# Remie_Schematic.net
KiCad netlist of a schematic drawn in Altium Designer
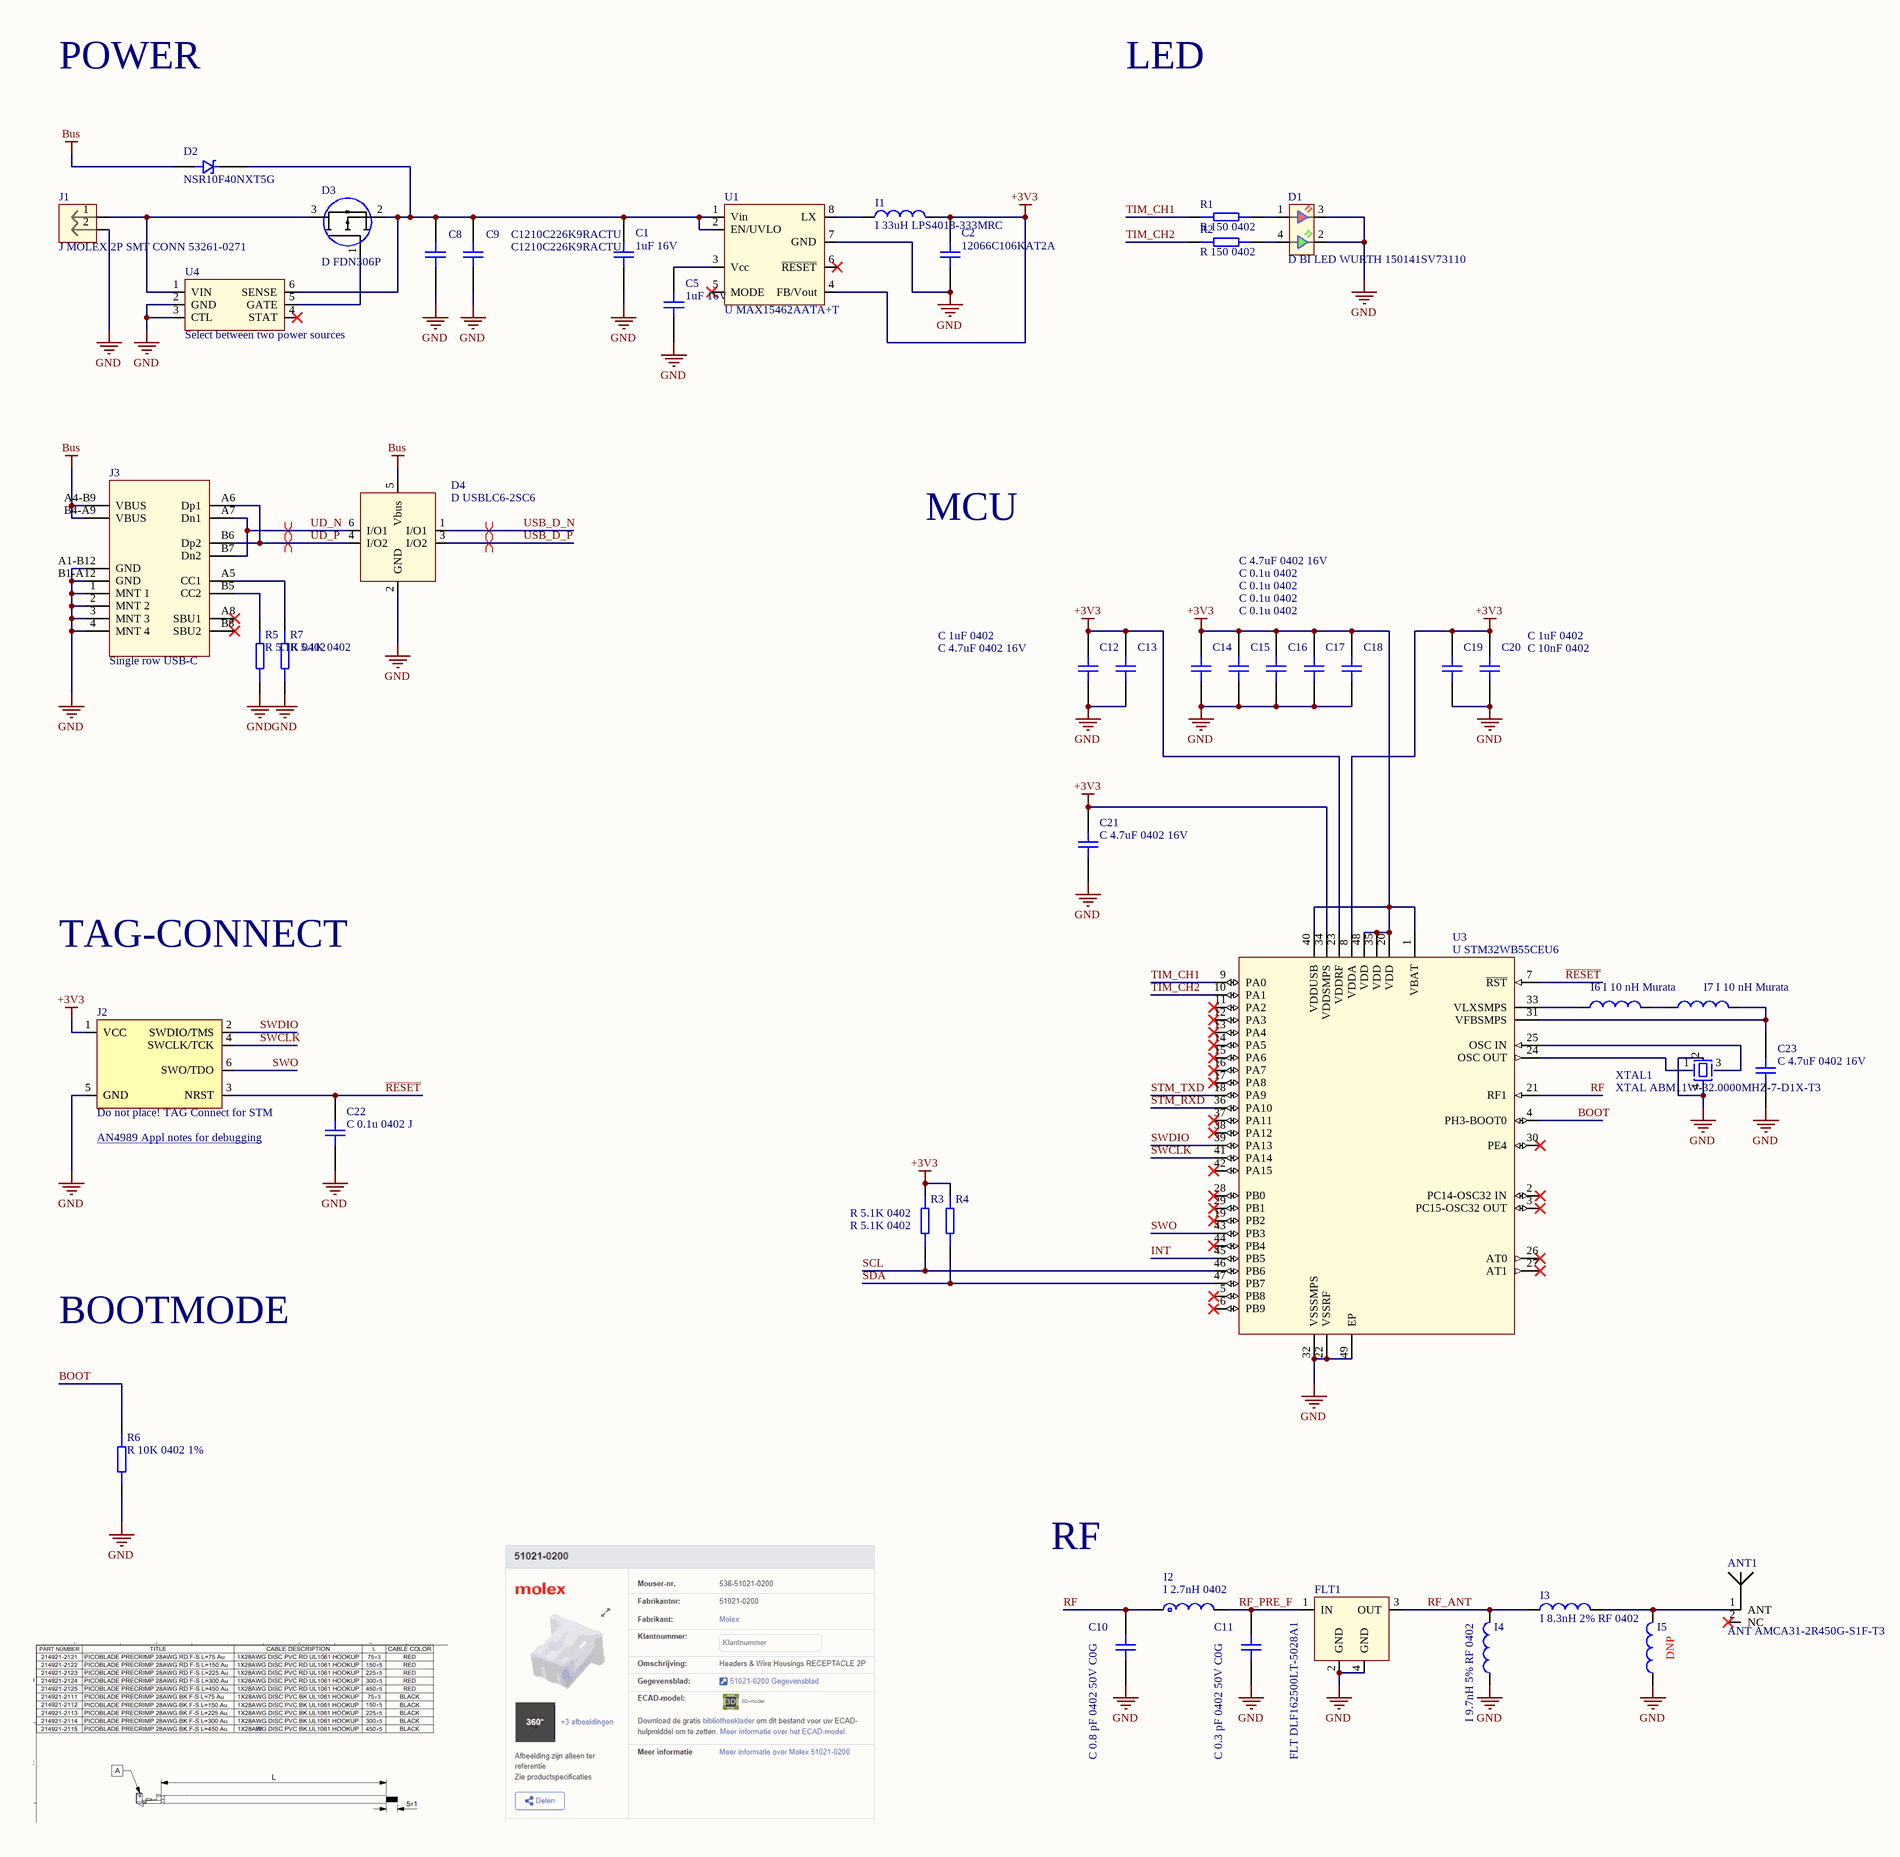
[diagram p0: Remie_Schematic.SchDoc, left]
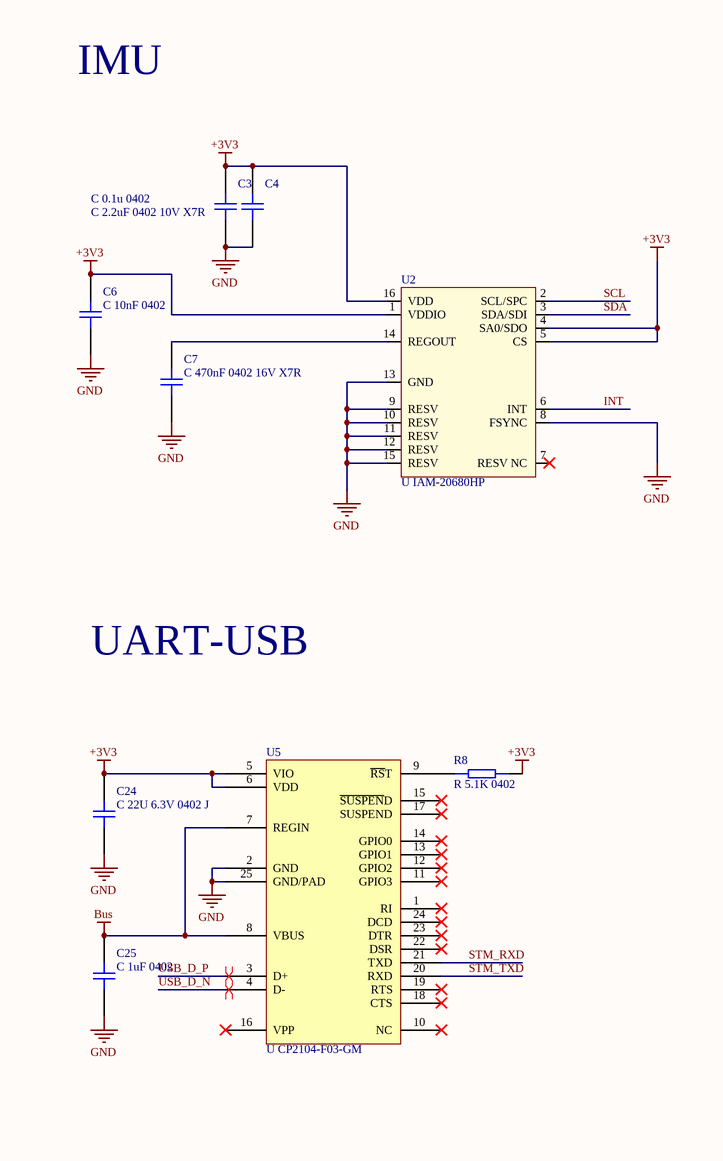
[diagram p1: Remie_Schematic.SchDoc, right]

(export (version "E")
  (design (tool "Eeschema 10.0.6"))
  (components
    (comp (ref "ANT1")
      (value "ANT AMCA31-2R450G-S1F-T3")
      (footprint "ABRACON AMCA31")
      (description "Chip Dielectric Antenna; 1dBi; 2450MHz; T/R ¦ Abracon AMCA31-2R450G-S1F-T3")
      (fields
        (field (name "MANUFACTURER") "Abracon")
        (field (name "MANUFACTURER PART NUMBER") "AMCA31-2R450G-S1F-T3")
      )
      (libsource (lib "Schlib2") (part "ANT AMCA31-2R450G-S1F-T3"))
    )
    (comp (ref "C1")
      (value "1uF 16V")
      (footprint "C0805")
      (description "Multilayer Ceramic Capacitor, 1 uF, 16 V, ± 10%, X7R, 0805 [2012 Metric]")
      (fields
        (field (name "MANUFACTURER") "KEMET")
        (field (name "MANUFACTURER PART NUMBER") "C0805C105K4RACTU")
      )
      (libsource (lib "Schlib2") (part "C 1U 0805 X7R 16V"))
    )
    (comp (ref "C2")
      (value "12066C106KAT2A")
      (footprint "C1206")
      (description "1206 6.3 V 10 uF ±10% Tolerance X7R SMT Multilayer Ceramic Capacitor")
      (fields (field (name "MANUFACTURER") "Kyocera AVX") (field (name "TOLERANCE") "10%"))
      (libsource (lib "Schlib2") (part "C 10uF 1206 6.3V X7R"))
    )
    (comp (ref "C3")
      (value "C 0.1u 0402")
      (footprint "C0402")
      (description "Multilayer Ceramic Capacitor, 0.1 uF, 50 V, ± 10%, X7R, 0402 [1005 Metric]")
      (fields
        (field (name "MANUFACTURER") "Samsung")
        (field (name "MANUFACTURER PART NUMBER") "CL05B104KB54PNC")
      )
      (libsource (lib "Schlib2") (part "C 0.1u 0402"))
    )
    (comp (ref "C4")
      (value "C 2.2uF 0402 10V X7R")
      (footprint "C0402")
      (description "Multilayer Ceramic Capacitor, 2.2 uF, 10 V, ± 10%, X7R, 0402 [1005 Metric] CC0402KRX5R7BB225")
      (fields
        (field (name "MANUFACTURER") "Yageo")
        (field (name "MANUFACTURER PART NUMBER") "CC0402KRX5R7BB225")
      )
      (libsource (lib "Schlib2") (part "C 2.2uF 0402 10V X7R"))
    )
    (comp (ref "C5")
      (value "1uF 16V")
      (footprint "C0805")
      (description "Multilayer Ceramic Capacitor, 1 uF, 16 V, ± 10%, X7R, 0805 [2012 Metric]")
      (fields
        (field (name "MANUFACTURER") "KEMET")
        (field (name "MANUFACTURER PART NUMBER") "C0805C105K4RACTU")
      )
      (libsource (lib "Schlib2") (part "C 1U 0805 X7R 16V"))
    )
    (comp (ref "C6")
      (value "C 10nF 0402")
      (footprint "C0402")
      (description "Multilayer Ceramic Capacitor, 0.01 uF, 50 V, ± 10%, X7R, 0402 [1005 Metric]")
      (fields
        (field (name "MANUFACTURER") "Samsung")
        (field (name "MANUFACTURER PART NUMBER") "CL05B103KB5NNNC")
      )
      (libsource (lib "Schlib2") (part "C 10nF 0402"))
    )
    (comp (ref "C7")
      (value "C 470nF 0402 16V X7R")
      (footprint "C0402")
      (description "Multilayer Ceramic Capacitor, 0.47 uF, 16 V, ± 10%, X7R, 0402 [1005 Metric] CC0402KRX7R5BB474")
      (fields
        (field (name "MANUFACTURER") "Yageo")
        (field (name "MANUFACTURER PART NUMBER") "CC0402KRX7R5BB474")
      )
      (libsource (lib "Schlib2") (part "C 470nF 0402 16V X7R"))
    )
    (comp (ref "C8")
      (value "C1210C226K9RACTU")
      (footprint "C1210")
      (description "Cap Ceramic 22uF 6.3V X7R 10% SMD 1210 125C Plastic T/R")
      (fields (field (name "MANUFACTURER") "KEMET") (field (name "TOLERANCE") "10%"))
      (libsource (lib "Schlib2") (part "C 22uF 1210 X7R 6.3V"))
    )
    (comp (ref "C9")
      (value "C1210C226K9RACTU")
      (footprint "C1210")
      (description "Cap Ceramic 22uF 6.3V X7R 10% SMD 1210 125C Plastic T/R")
      (fields (field (name "MANUFACTURER") "KEMET") (field (name "TOLERANCE") "10%"))
      (libsource (lib "Schlib2") (part "C 22uF 1210 X7R 6.3V"))
    )
    (comp (ref "C10")
      (value "C 0.8 pF 0402 50V C0G")
      (footprint "C0402")
      (fields
        (field (name "MANUFACTURER") "Murata")
        (field (name "MANUFACTURER PART NUMBER") "GRM1555C1HR80BA01D")
        (field (name "VOLTAGE") "50V")
      )
      (libsource (lib "Schlib2") (part "C 0.8 pF 0402 50V C0G"))
    )
    (comp (ref "C11")
      (value "C 0.3 pF 0402 50V C0G")
      (footprint "C0402")
      (description "Cap Ceramic 0.3pF 50V C0G 0.05pF Pad SMD 0402 125°C T/R")
      (fields
        (field (name "MANUFACTURER") "Murata")
        (field (name "MANUFACTURER PART NUMBER") "GRM1555C1HR30WA01D")
      )
      (libsource (lib "Schlib2") (part "C 0.3 pF 0402 50V C0G"))
    )
    (comp (ref "C12")
      (value "C 1uF 0402")
      (footprint "C0402")
      (description "Multilayer Ceramic Capacitor, 1 uF, 10 V, ± 10%, X5R, 0402 [1005 Metric]")
      (fields
        (field (name "MANUFACTURER") "Samsung")
        (field (name "MANUFACTURER PART NUMBER") "CL05A105KP5NNNC")
      )
      (libsource (lib "Schlib2") (part "C 1uF 0402"))
    )
    (comp (ref "C13")
      (value "C 4.7uF 0402 16V")
      (footprint "C0402")
      (description "Multilayer Ceramic Capacitor, 4.7 uF, 16 V, ± 20%, X5R, 0402 [1005 Metric] CL05A475MO5NUNC")
      (fields
        (field (name "MANUFACTURER") "Samsung")
        (field (name "MANUFACTURER PART NUMBER") "CL05A475MO5NUNC")
      )
      (libsource (lib "Schlib2") (part "C 4.7uF 0402 16V"))
    )
    (comp (ref "C14")
      (value "C 4.7uF 0402 16V")
      (footprint "C0402")
      (description "Multilayer Ceramic Capacitor, 4.7 uF, 16 V, ± 20%, X5R, 0402 [1005 Metric] CL05A475MO5NUNC")
      (fields
        (field (name "MANUFACTURER") "Samsung")
        (field (name "MANUFACTURER PART NUMBER") "CL05A475MO5NUNC")
      )
      (libsource (lib "Schlib2") (part "C 4.7uF 0402 16V"))
    )
    (comp (ref "C15")
      (value "C 0.1u 0402")
      (footprint "C0402")
      (description "Multilayer Ceramic Capacitor, 0.1 uF, 50 V, ± 10%, X7R, 0402 [1005 Metric]")
      (fields
        (field (name "MANUFACTURER") "Samsung")
        (field (name "MANUFACTURER PART NUMBER") "CL05B104KB54PNC")
      )
      (libsource (lib "Schlib2") (part "C 0.1u 0402"))
    )
    (comp (ref "C16")
      (value "C 0.1u 0402")
      (footprint "C0402")
      (description "Multilayer Ceramic Capacitor, 0.1 uF, 50 V, ± 10%, X7R, 0402 [1005 Metric]")
      (fields
        (field (name "MANUFACTURER") "Samsung")
        (field (name "MANUFACTURER PART NUMBER") "CL05B104KB54PNC")
      )
      (libsource (lib "Schlib2") (part "C 0.1u 0402"))
    )
    (comp (ref "C17")
      (value "C 0.1u 0402")
      (footprint "C0402")
      (description "Multilayer Ceramic Capacitor, 0.1 uF, 50 V, ± 10%, X7R, 0402 [1005 Metric]")
      (fields
        (field (name "MANUFACTURER") "Samsung")
        (field (name "MANUFACTURER PART NUMBER") "CL05B104KB54PNC")
      )
      (libsource (lib "Schlib2") (part "C 0.1u 0402"))
    )
    (comp (ref "C18")
      (value "C 0.1u 0402")
      (footprint "C0402")
      (description "Multilayer Ceramic Capacitor, 0.1 uF, 50 V, ± 10%, X7R, 0402 [1005 Metric]")
      (fields
        (field (name "MANUFACTURER") "Samsung")
        (field (name "MANUFACTURER PART NUMBER") "CL05B104KB54PNC")
      )
      (libsource (lib "Schlib2") (part "C 0.1u 0402"))
    )
    (comp (ref "C19")
      (value "C 1uF 0402")
      (footprint "C0402")
      (description "Multilayer Ceramic Capacitor, 1 uF, 10 V, ± 10%, X5R, 0402 [1005 Metric]")
      (fields
        (field (name "MANUFACTURER") "Samsung")
        (field (name "MANUFACTURER PART NUMBER") "CL05A105KP5NNNC")
      )
      (libsource (lib "Schlib2") (part "C 1uF 0402"))
    )
    (comp (ref "C20")
      (value "C 10nF 0402")
      (footprint "C0402")
      (description "Multilayer Ceramic Capacitor, 0.01 uF, 50 V, ± 10%, X7R, 0402 [1005 Metric]")
      (fields
        (field (name "MANUFACTURER") "Samsung")
        (field (name "MANUFACTURER PART NUMBER") "CL05B103KB5NNNC")
      )
      (libsource (lib "Schlib2") (part "C 10nF 0402"))
    )
    (comp (ref "C21")
      (value "C 4.7uF 0402 16V")
      (footprint "C0402")
      (description "Multilayer Ceramic Capacitor, 4.7 uF, 16 V, ± 20%, X5R, 0402 [1005 Metric] CL05A475MO5NUNC")
      (fields
        (field (name "MANUFACTURER") "Samsung")
        (field (name "MANUFACTURER PART NUMBER") "CL05A475MO5NUNC")
      )
      (libsource (lib "Schlib2") (part "C 4.7uF 0402 16V"))
    )
    (comp (ref "C22")
      (value "C 0.1u 0402 J")
      (footprint "C0402")
      (description "Cap Ceramic 0.1uF 50V X7R 10% Pad SMD 0402 125C Low ESR Automotive CL05B104KB54PNC")
      (fields
        (field (name "MANUFACTURER") "Samsung")
        (field (name "MANUFACTURER PART NUMBER") "CL05B104KB54PNC")
      )
      (libsource (lib "Schlib2") (part "C 0.1u 0402 J"))
    )
    (comp (ref "C23")
      (value "C 4.7uF 0402 16V")
      (footprint "C0402")
      (description "Multilayer Ceramic Capacitor, 4.7 uF, 16 V, ± 20%, X5R, 0402 [1005 Metric] CL05A475MO5NUNC")
      (fields
        (field (name "MANUFACTURER") "Samsung")
        (field (name "MANUFACTURER PART NUMBER") "CL05A475MO5NUNC")
      )
      (libsource (lib "Schlib2") (part "C 4.7uF 0402 16V"))
    )
    (comp (ref "C24")
      (value "C 22U 6.3V 0402 J")
      (footprint "C0402")
      (description "CAP CER 22F 6.3V X5R 0402 CM05X5R226M06AH080")
      (fields
        (field (name "MANUFACTURER") "Kyocera AVX")
        (field (name "MANUFACTURER PART NUMBER") "CM05X5R226M06AH080")
      )
      (libsource (lib "Schlib2") (part "C 22U 6.3V 0402 J"))
    )
    (comp (ref "C25")
      (value "C 1uF 0402")
      (footprint "C0402")
      (description "Multilayer Ceramic Capacitor, 1 uF, 10 V, ± 10%, X5R, 0402 [1005 Metric]")
      (fields
        (field (name "MANUFACTURER") "Samsung")
        (field (name "MANUFACTURER PART NUMBER") "CL05A105KP5NNNC")
      )
      (libsource (lib "Schlib2") (part "C 1uF 0402"))
    )
    (comp (ref "D1")
      (value "D BI LED WURTH 150141SV73110")
      (footprint "Wurth 150141SV73110")
      (description "WL-SBTW SMT bi-color TOP LED waterclear")
      (fields
        (field (name "MANUFACTURER") "Wurth Electronics")
        (field (name "MANUFACTURER PART NUMBER") "150141SV73110")
      )
      (libsource (lib "Schlib2") (part "D BI LED WURTH 150141SV73110"))
    )
    (comp (ref "D2")
      (value "NSR10F40NXT5G")
      (footprint "SCHOTTKY NSR10")
      (fields (field (name "MANUFACTURER") "ON Semiconductor"))
      (libsource (lib "Schlib2") (part "D Schottky 1A"))
    )
    (comp (ref "D3")
      (value "D FDN306P")
      (footprint "SOT23")
      (description "P-Channel PowerTrench® MOSFET, 1.8V Specified, -12V, -2.6A, 40mΩ")
      (fields
        (field (name "MANUFACTURER") "ON Semiconductor / Fairchild")
        (field (name "MANUFACTURER PART NUMBER") "FDN306P")
      )
      (libsource (lib "Schlib2") (part "D FDN306P"))
    )
    (comp (ref "D4")
      (value "D USBLC6-2SC6")
      (footprint "SOT23-6L")
      (description "USBLC6 Series 2 Line 6 V Uni / Bi-Directional ESD Protection - SOT-23-6")
      (fields
        (field (name "MANUFACTURER") "STMicroelectronics")
        (field (name "MANUFACTURER PART NUMBER") "USBLC6-2SC6")
      )
      (libsource (lib "Schlib2") (part "D USBLC6-2SC6"))
    )
    (comp (ref "FLT1")
      (value "FLT DLF162500LT-5028A1")
      (footprint "TDK DLF Series")
      (description "FILTER, LOW PASS, 2.4GHz to 2.5GHz; Filter Type: Low Pass; Pass Band Frequency: 2.")
      (fields
        (field (name "MANUFACTURER") "TDK")
        (field (name "MANUFACTURER PART NUMBER") "DLF162500LT-5028A1")
      )
      (libsource (lib "Schlib2") (part "FLT DLF162500LT-5028A1"))
    )
    (comp (ref "I1")
      (value "I 33uH LPS4018-333MRC")
      (footprint "COILCRAFT LPS4018")
      (description "Power inductor, shielded, 20/30% tol, SMT, RoHS, lead-free, halogen-free LPS4018-333MRC Isat 0.58A")
      (fields
        (field (name "MANUFACTURER") "Coilcraft")
        (field (name "MANUFACTURER PART NUMBER") "LPS4018-333MRC")
      )
      (libsource (lib "Schlib2") (part "I 33uH LPS4018-333MRC"))
    )
    (comp (ref "I2")
      (value "I 2.7nH 0402")
      (footprint "I0402 POL")
      (description "0402 2.7nH ±0.3nH DCR=120mΩ Q=8@100MHz 800mA SRF=6GHz LQG15HS2N7S02D")
      (fields
        (field (name "MANUFACTURER") "Murata")
        (field (name "MANUFACTURER PART NUMBER") "LQG15HS2N7S02D")
      )
      (libsource (lib "Schlib2") (part "I 2.7nH 0402"))
    )
    (comp (ref "I3")
      (value "I 8.3nH 2% RF 0402")
      (footprint "R0402")
      (description "Ind Chip Wirewound 8.3nH 0.2nH 0402 Paper T/R LQW15AN8N3C1ZD")
      (fields
        (field (name "MANUFACTURER") "Murata")
        (field (name "MANUFACTURER PART NUMBER") "LQW15AN8N3C1ZD")
      )
      (libsource (lib "Schlib2") (part "I 8.3nH 2% RF 0402"))
    )
    (comp (ref "I4")
      (value "I 9.7nH 5% RF 0402")
      (footprint "R0402")
      (description "Ind Chip Wirewound 9.7nH 5% 0402 Paper T/R LQW15AN9N7J0ZD")
      (fields
        (field (name "MANUFACTURER") "Murata")
        (field (name "MANUFACTURER PART NUMBER") "LQW15AN9N7J0ZD")
      )
      (libsource (lib "Schlib2") (part "I 9.7nH 5% RF 0402"))
    )
    (comp (ref "I5")
      (value "I 9.7nH 5% RF 0402")
      (footprint "R0402")
      (description "Ind Chip Wirewound 9.7nH 5% 0402 Paper T/R LQW15AN9N7J0ZD")
      (fields
        (field (name "MANUFACTURER") "Murata")
        (field (name "MANUFACTURER PART NUMBER") "LQW15AN9N7J0ZD")
      )
      (libsource (lib "Schlib2") (part "I 9.7nH 5% RF 0402"))
    )
    (comp (ref "I6")
      (value "I 10 nH Murata")
      (footprint "MURATA LQG15XXX IND")
      (fields
        (field (name "MANUFACTURER") "Murata")
        (field (name "MANUFACTURER PART NUMBER") "LQG15WZ10NJ02D")
        (field (name "TOLERANCE") "5%")
      )
      (libsource (lib "Schlib2") (part "I 10 nH Murata"))
    )
    (comp (ref "I7")
      (value "I 10 nH Murata")
      (footprint "MURATA LQG15XXX IND")
      (fields
        (field (name "MANUFACTURER") "Murata")
        (field (name "MANUFACTURER PART NUMBER") "LQG15WZ10NJ02D")
        (field (name "TOLERANCE") "5%")
      )
      (libsource (lib "Schlib2") (part "I 10 nH Murata"))
    )
    (comp (ref "J1")
      (value "J MOLEX 2P SMT CONN 53261-0271")
      (footprint "MOLEX 532610271")
      (description "1.25mm Pitch PicoBlade™ Header, Surface Mount, Right Angle, Lead-Free, 2 Circuits")
      (fields (field (name "MANUFACTURER") "Molex") (field (name "MANUFACTURER PART NUMBER") "53261-0271"))
      (libsource (lib "Schlib2") (part "J MOLEX 2P SMT CONN 53261-0271"))
    )
    (comp (ref "J2")
      (value "Do not place! TAG Connect for STM")
      (footprint "TAG-CONNECT-6")
      (libsource (lib "Schlib2") (part "J TAG for STM TC-2030"))
    )
    (comp (ref "J3")
      (value "Single row USB-C")
      (footprint "FP-USB4105-GF-A-MFG")
      (description "Conn USB 2.0 Type C RCP 24 POS 0.3mm/0.5mm Solder RA SMD 24 Terminal 1 Port T/R")
      (fields
        (field (name "MANUFACTURER") "Global Connector Technology")
        (field (name "MANUFACTURER PART NUMBER") "USB4105-GF-A")
      )
      (libsource (lib "Schlib2") (part "J USB4105-GF-A"))
    )
    (comp (ref "R1")
      (value "R 150 0402")
      (footprint "R0402")
      (description "SMD Chip Resistor, 150 Ohm, ± 1%, 62.5 mW, 0402 [1005 Metric], Thick Film, General Purpose")
      (fields
        (field (name "MANUFACTURER") "Yageo")
        (field (name "MANUFACTURER PART NUMBER") "RC0402FR-07150RL")
      )
      (libsource (lib "Schlib2") (part "R 150 0402"))
    )
    (comp (ref "R2")
      (value "R 150 0402")
      (footprint "R0402")
      (description "SMD Chip Resistor, 150 Ohm, ± 1%, 62.5 mW, 0402 [1005 Metric], Thick Film, General Purpose")
      (fields
        (field (name "MANUFACTURER") "Yageo")
        (field (name "MANUFACTURER PART NUMBER") "RC0402FR-07150RL")
      )
      (libsource (lib "Schlib2") (part "R 150 0402"))
    )
    (comp (ref "R3")
      (value "R 5.1K 0402")
      (footprint "R0402")
      (fields
        (field (name "MANUFACTURER") "Vishay")
        (field (name "MANUFACTURER PART NUMBER") "CRCW04025K10FKED")
        (field (name "TOLERANCE") "1%")
      )
      (libsource (lib "Schlib2") (part "R 5.1K 0402"))
    )
    (comp (ref "R4")
      (value "R 5.1K 0402")
      (footprint "R0402")
      (fields
        (field (name "MANUFACTURER") "Vishay")
        (field (name "MANUFACTURER PART NUMBER") "CRCW04025K10FKED")
        (field (name "TOLERANCE") "1%")
      )
      (libsource (lib "Schlib2") (part "R 5.1K 0402"))
    )
    (comp (ref "R5")
      (value "R 5.1K 0402")
      (footprint "R0402")
      (fields
        (field (name "MANUFACTURER") "Vishay")
        (field (name "MANUFACTURER PART NUMBER") "CRCW04025K10FKED")
        (field (name "TOLERANCE") "1%")
      )
      (libsource (lib "Schlib2") (part "R 5.1K 0402"))
    )
    (comp (ref "R6")
      (value "R 10K 0402 1%")
      (footprint "R0402")
      (description "Res Thick Film 0402 10K Ohm 1% 0.2W(1/5W) ±100ppm/°C Pad SMD Automotive T/R CRCW040210K0FKEDHP")
      (fields
        (field (name "MANUFACTURER") "Vishay Dale")
        (field (name "MANUFACTURER PART NUMBER") "CRCW040210K0FKEDHP")
      )
      (libsource (lib "Schlib2") (part "R 10K 0402 1%"))
    )
    (comp (ref "R7")
      (value "R 5.1K 0402")
      (footprint "R0402")
      (fields
        (field (name "MANUFACTURER") "Vishay")
        (field (name "MANUFACTURER PART NUMBER") "CRCW04025K10FKED")
        (field (name "TOLERANCE") "1%")
      )
      (libsource (lib "Schlib2") (part "R 5.1K 0402"))
    )
    (comp (ref "R8")
      (value "R 5.1K 0402")
      (footprint "R0402")
      (fields
        (field (name "MANUFACTURER") "Vishay")
        (field (name "MANUFACTURER PART NUMBER") "CRCW04025K10FKED")
        (field (name "TOLERANCE") "1%")
      )
      (libsource (lib "Schlib2") (part "R 5.1K 0402"))
    )
    (comp (ref "U1")
      (value "U MAX15462AATA+T")
      (footprint "8TDFN-CU")
      (description "IC Reg Buck 3.3V 300MA 8TDFN")
      (fields
        (field (name "MANUFACTURER") "Analog Devices")
        (field (name "MANUFACTURER PART NUMBER") "MAX15462AATA+T")
      )
      (libsource (lib "Schlib2") (part "U MAX15462AATA+T"))
    )
    (comp (ref "U2")
      (value "U IAM-20680HP")
      (footprint "IAM-20680HP")
      (description "IMU (Inertial Measurement Unit), 6-Axis, Accelerometer, Gyroscope IAM-20680HP")
      (fields (field (name "MANUFACTURER") "TDK") (field (name "MANUFACTURER PART NUMBER") "IAM-20680HP"))
      (libsource (lib "Schlib2") (part "U IAM-20680HP"))
    )
    (comp (ref "U3")
      (value "U STM32WB55CEU6")
      (footprint "STM32WB55xx VFQFPN58")
      (description "Bluetooth v5.0 and 802.15.4 With Microcontroller Combo module")
      (fields
        (field (name "MANUFACTURER") "STMicroelectronics")
        (field (name "MANUFACTURER PART NUMBER") "STM32WB55CEU6")
      )
      (libsource (lib "Schlib2") (part "U STM32WB55CEU6"))
    )
    (comp (ref "U4")
      (value "Select between two power sources")
      (footprint "TSOT-23")
      (fields
        (field (name "MANUFACTURER") "Analog Devices / Linear Technology")
        (field (name "MANUFACTURER PART NUMBER") "LTC4412HVIS6#TRMPBF")
      )
      (libsource (lib "Schlib2") (part "U LTC4412HVIS6#TRMPBF"))
    )
    (comp (ref "U5")
      (value "U CP2104-F03-GM")
      (footprint "QFN24-CP2104")
      (description "IC SGL USB-TO-UART BRIDGE 24QFN")
      (fields
        (field (name "MANUFACTURER") "Silicon Labs")
        (field (name "MANUFACTURER PART NUMBER") "CP2104-F03-GM")
      )
      (libsource (lib "Schlib1") (part "U CP2104-F03-GM"))
    )
    (comp (ref "XTAL1")
      (value "XTAL ABM11W-32.0000MHZ-7-D1X-T3")
      (footprint "ABRACON ABM11W CRYSTALS")
      (description "Crystal 32MHz 7pF 4-Pin CSMD T/R")
      (fields
        (field (name "MANUFACTURER") "Abracon")
        (field (name "MANUFACTURER PART NUMBER") "ABM11W-32.0000MHZ-7-D1X-T3")
      )
      (libsource (lib "Schlib2") (part "XTAL ABM11W-32.0000MHZ-7-D1X-T3"))
    )
  )
  (nets
    (net (code "1") (name "+3V3") (class "Default")
      (node (ref "C12") (pin "2") (pinfunction "2_2") (pintype "passive"))
      (node (ref "C13") (pin "2") (pinfunction "2_2") (pintype "passive"))
      (node (ref "C14") (pin "2") (pinfunction "2_2") (pintype "passive"))
      (node (ref "C15") (pin "2") (pinfunction "2_2") (pintype "passive"))
      (node (ref "C16") (pin "2") (pinfunction "2_2") (pintype "passive"))
      (node (ref "C17") (pin "2") (pinfunction "2_2") (pintype "passive"))
      (node (ref "C18") (pin "2") (pinfunction "2_2") (pintype "passive"))
      (node (ref "C19") (pin "2") (pinfunction "2_2") (pintype "passive"))
      (node (ref "C2") (pin "2") (pinfunction "2_2") (pintype "passive"))
      (node (ref "C20") (pin "2") (pinfunction "2_2") (pintype "passive"))
      (node (ref "C21") (pin "2") (pinfunction "2_2") (pintype "passive"))
      (node (ref "C24") (pin "2") (pinfunction "2_2") (pintype "passive"))
      (node (ref "C3") (pin "2") (pinfunction "2_2") (pintype "passive"))
      (node (ref "C4") (pin "2") (pinfunction "2_2") (pintype "passive"))
      (node (ref "C6") (pin "2") (pinfunction "2_2") (pintype "passive"))
      (node (ref "I1") (pin "2") (pinfunction "2_2") (pintype "passive"))
      (node (ref "J2") (pin "1") (pinfunction "VCC_1") (pintype "passive"))
      (node (ref "R3") (pin "2") (pinfunction "2_2") (pintype "passive"))
      (node (ref "R4") (pin "2") (pinfunction "2_2") (pintype "passive"))
      (node (ref "R8") (pin "2") (pinfunction "2_2") (pintype "passive"))
      (node (ref "U1") (pin "4") (pinfunction "FB/Vout_4") (pintype "passive"))
      (node (ref "U2") (pin "1") (pinfunction "VDDIO_1") (pintype "passive"))
      (node (ref "U2") (pin "16") (pinfunction "VDD_16") (pintype "passive"))
      (node (ref "U2") (pin "4") (pinfunction "SA0/SDO_4") (pintype "passive"))
      (node (ref "U2") (pin "5") (pinfunction "CS_5") (pintype "passive"))
      (node (ref "U3") (pin "1") (pinfunction "VBAT_1") (pintype "power_in"))
      (node (ref "U3") (pin "20") (pinfunction "VDD_20") (pintype "power_in"))
      (node (ref "U3") (pin "23") (pinfunction "VDDRF_23") (pintype "power_in"))
      (node (ref "U3") (pin "34") (pinfunction "VDDSMPS_34") (pintype "power_in"))
      (node (ref "U3") (pin "35") (pinfunction "VDD_35") (pintype "power_in"))
      (node (ref "U3") (pin "40") (pinfunction "VDDUSB_40") (pintype "power_in"))
      (node (ref "U3") (pin "48") (pinfunction "VDD_48") (pintype "power_in"))
      (node (ref "U3") (pin "8") (pinfunction "VDDA_8") (pintype "power_in"))
      (node (ref "U5") (pin "5") (pinfunction "VIO_5") (pintype "passive"))
      (node (ref "U5") (pin "6") (pinfunction "VDD_6") (pintype "passive"))
    )
    (net (code "2") (name "/BOOT") (class "Default")
      (node (ref "R6") (pin "2") (pinfunction "2_2") (pintype "passive"))
      (node (ref "U3") (pin "4") (pinfunction "PH3-BOOT0_4") (pintype "bidirectional"))
    )
    (net (code "3") (name "/INT") (class "Default")
      (node (ref "U2") (pin "6") (pinfunction "INT_6") (pintype "passive"))
      (node (ref "U3") (pin "45") (pinfunction "PB5_45") (pintype "bidirectional"))
    )
    (net (code "4") (name "/RF") (class "Default")
      (node (ref "C10") (pin "2") (pinfunction "2_2") (pintype "passive"))
      (node (ref "I2") (pin "1") (pinfunction "1_1") (pintype "passive"))
      (node (ref "U3") (pin "21") (pinfunction "RF1_21") (pintype "input"))
    )
    (net (code "5") (name "/RF_ANT") (class "Default")
      (node (ref "FLT1") (pin "3") (pinfunction "OUT_3") (pintype "passive"))
      (node (ref "I3") (pin "1") (pinfunction "1_1") (pintype "passive"))
      (node (ref "I4") (pin "2") (pinfunction "2_2") (pintype "passive"))
    )
    (net (code "6") (name "/RF_PRE_F") (class "Default")
      (node (ref "C11") (pin "2") (pinfunction "2_2") (pintype "passive"))
      (node (ref "FLT1") (pin "1") (pinfunction "IN_1") (pintype "passive"))
      (node (ref "I2") (pin "2") (pinfunction "2_2") (pintype "passive"))
    )
    (net (code "7") (name "/SCL") (class "Default")
      (node (ref "R3") (pin "1") (pinfunction "1_1") (pintype "passive"))
      (node (ref "U2") (pin "2") (pinfunction "SCL/SPC_2") (pintype "passive"))
      (node (ref "U3") (pin "46") (pinfunction "PB6_46") (pintype "bidirectional"))
    )
    (net (code "8") (name "/SDA") (class "Default")
      (node (ref "R4") (pin "1") (pinfunction "1_1") (pintype "passive"))
      (node (ref "U2") (pin "3") (pinfunction "SDA/SDI_3") (pintype "passive"))
      (node (ref "U3") (pin "47") (pinfunction "PB7_47") (pintype "bidirectional"))
    )
    (net (code "9") (name "/STM_RXD") (class "Default")
      (node (ref "U3") (pin "36") (pinfunction "PA10_36") (pintype "bidirectional"))
      (node (ref "U5") (pin "21") (pinfunction "TXD_21") (pintype "passive"))
    )
    (net (code "10") (name "/STM_TXD") (class "Default")
      (node (ref "U3") (pin "18") (pinfunction "PA9_18") (pintype "bidirectional"))
      (node (ref "U5") (pin "20") (pinfunction "RXD_20") (pintype "passive"))
    )
    (net (code "11") (name "/SWCLK") (class "Default")
      (node (ref "J2") (pin "4") (pinfunction "SWCLK/TCK_4") (pintype "passive"))
      (node (ref "U3") (pin "41") (pinfunction "PA14_41") (pintype "bidirectional"))
    )
    (net (code "12") (name "/SWDIO") (class "Default")
      (node (ref "J2") (pin "2") (pinfunction "SWDIO/TMS_2") (pintype "passive"))
      (node (ref "U3") (pin "39") (pinfunction "PA13_39") (pintype "bidirectional"))
    )
    (net (code "13") (name "/SWO") (class "Default")
      (node (ref "J2") (pin "6") (pinfunction "SWO/TDO_6") (pintype "passive"))
      (node (ref "U3") (pin "43") (pinfunction "PB3_43") (pintype "bidirectional"))
    )
    (net (code "14") (name "/TIM_CH1") (class "Default")
      (node (ref "R1") (pin "1") (pinfunction "1_1") (pintype "passive"))
      (node (ref "U3") (pin "9") (pinfunction "PA0_9") (pintype "bidirectional"))
    )
    (net (code "15") (name "/TIM_CH2") (class "Default")
      (node (ref "R2") (pin "1") (pinfunction "1_1") (pintype "passive"))
      (node (ref "U3") (pin "10") (pinfunction "PA1_10") (pintype "bidirectional"))
    )
    (net (code "16") (name "/UD_N") (class "Default")
      (node (ref "D4") (pin "6") (pinfunction "I/O1_6") (pintype "passive"))
      (node (ref "J3") (pin "A7") (pinfunction "Dn1_A7") (pintype "passive"))
      (node (ref "J3") (pin "B7") (pinfunction "Dn2_B7") (pintype "passive"))
    )
    (net (code "17") (name "/UD_P") (class "Default")
      (node (ref "D4") (pin "4") (pinfunction "I/O2_4") (pintype "passive"))
      (node (ref "J3") (pin "A6") (pinfunction "Dp1_A6") (pintype "passive"))
      (node (ref "J3") (pin "B6") (pinfunction "Dp2_B6") (pintype "passive"))
    )
    (net (code "18") (name "/USB_D_N") (class "Default")
      (node (ref "D4") (pin "1") (pinfunction "I/O1_1") (pintype "passive"))
      (node (ref "U5") (pin "4") (pinfunction "D-_4") (pintype "passive"))
    )
    (net (code "19") (name "/USB_D_P") (class "Default")
      (node (ref "D4") (pin "3") (pinfunction "I/O2_3") (pintype "passive"))
      (node (ref "U5") (pin "3") (pinfunction "D+_3") (pintype "passive"))
    )
    (net (code "20") (name "/~{RESET}") (class "Default")
      (node (ref "C22") (pin "2") (pinfunction "2_2") (pintype "passive"))
      (node (ref "J2") (pin "3") (pinfunction "NRST_3") (pintype "passive"))
      (node (ref "U3") (pin "7") (pinfunction "~{RST}_7") (pintype "input"))
    )
    (net (code "21") (name "Bus") (class "Default")
      (node (ref "C25") (pin "2") (pinfunction "2_2") (pintype "passive"))
      (node (ref "D2") (pin "A") (pinfunction "A_A") (pintype "passive"))
      (node (ref "D4") (pin "5") (pinfunction "Vbus_5") (pintype "passive"))
      (node (ref "J3") (pin "A4-B9") (pinfunction "VBUS_A4-B9") (pintype "passive"))
      (node (ref "J3") (pin "B4-A9") (pinfunction "VBUS_B4-A9") (pintype "passive"))
      (node (ref "U5") (pin "7") (pinfunction "REGIN_7") (pintype "passive"))
      (node (ref "U5") (pin "8") (pinfunction "VBUS_8") (pintype "passive"))
    )
    (net (code "22") (name "GND") (class "Default")
      (node (ref "C1") (pin "1") (pinfunction "1_1") (pintype "passive"))
      (node (ref "C10") (pin "1") (pinfunction "1_1") (pintype "passive"))
      (node (ref "C11") (pin "1") (pinfunction "1_1") (pintype "passive"))
      (node (ref "C12") (pin "1") (pinfunction "1_1") (pintype "passive"))
      (node (ref "C13") (pin "1") (pinfunction "1_1") (pintype "passive"))
      (node (ref "C14") (pin "1") (pinfunction "1_1") (pintype "passive"))
      (node (ref "C15") (pin "1") (pinfunction "1_1") (pintype "passive"))
      (node (ref "C16") (pin "1") (pinfunction "1_1") (pintype "passive"))
      (node (ref "C17") (pin "1") (pinfunction "1_1") (pintype "passive"))
      (node (ref "C18") (pin "1") (pinfunction "1_1") (pintype "passive"))
      (node (ref "C19") (pin "1") (pinfunction "1_1") (pintype "passive"))
      (node (ref "C2") (pin "1") (pinfunction "1_1") (pintype "passive"))
      (node (ref "C20") (pin "1") (pinfunction "1_1") (pintype "passive"))
      (node (ref "C21") (pin "1") (pinfunction "1_1") (pintype "passive"))
      (node (ref "C22") (pin "1") (pinfunction "1_1") (pintype "passive"))
      (node (ref "C23") (pin "1") (pinfunction "1_1") (pintype "passive"))
      (node (ref "C24") (pin "1") (pinfunction "1_1") (pintype "passive"))
      (node (ref "C25") (pin "1") (pinfunction "1_1") (pintype "passive"))
      (node (ref "C3") (pin "1") (pinfunction "1_1") (pintype "passive"))
      (node (ref "C4") (pin "1") (pinfunction "1_1") (pintype "passive"))
      (node (ref "C5") (pin "1") (pinfunction "1_1") (pintype "passive"))
      (node (ref "C6") (pin "1") (pinfunction "1_1") (pintype "passive"))
      (node (ref "C7") (pin "1") (pinfunction "1_1") (pintype "passive"))
      (node (ref "C8") (pin "1") (pinfunction "1_1") (pintype "passive"))
      (node (ref "C9") (pin "1") (pinfunction "1_1") (pintype "passive"))
      (node (ref "D1") (pin "2") (pinfunction "2_2") (pintype "passive"))
      (node (ref "D1") (pin "3") (pinfunction "3_3") (pintype "passive"))
      (node (ref "D4") (pin "2") (pinfunction "GND_2") (pintype "passive"))
      (node (ref "FLT1") (pin "2") (pinfunction "GND_2") (pintype "passive"))
      (node (ref "FLT1") (pin "4") (pinfunction "GND_4") (pintype "passive"))
      (node (ref "I4") (pin "1") (pinfunction "1_1") (pintype "passive"))
      (node (ref "I5") (pin "1") (pinfunction "1_1") (pintype "passive"))
      (node (ref "J1") (pin "2") (pinfunction "2_2") (pintype "passive"))
      (node (ref "J2") (pin "5") (pinfunction "GND_5") (pintype "passive"))
      (node (ref "J3") (pin "1") (pinfunction "MNT_1_1") (pintype "passive"))
      (node (ref "J3") (pin "2") (pinfunction "MNT_2_2") (pintype "passive"))
      (node (ref "J3") (pin "3") (pinfunction "MNT_3_3") (pintype "passive"))
      (node (ref "J3") (pin "4") (pinfunction "MNT_4_4") (pintype "passive"))
      (node (ref "J3") (pin "A1-B12") (pinfunction "GND_A1-B12") (pintype "passive"))
      (node (ref "J3") (pin "B1-A12") (pinfunction "GND_B1-A12") (pintype "passive"))
      (node (ref "R5") (pin "1") (pinfunction "1_1") (pintype "passive"))
      (node (ref "R6") (pin "1") (pinfunction "1_1") (pintype "passive"))
      (node (ref "R7") (pin "1") (pinfunction "1_1") (pintype "passive"))
      (node (ref "U1") (pin "7") (pinfunction "GND_7") (pintype "passive"))
      (node (ref "U2") (pin "10") (pinfunction "RESV_10") (pintype "passive"))
      (node (ref "U2") (pin "11") (pinfunction "RESV_11") (pintype "passive"))
      (node (ref "U2") (pin "12") (pinfunction "RESV_12") (pintype "passive"))
      (node (ref "U2") (pin "13") (pinfunction "GND_13") (pintype "passive"))
      (node (ref "U2") (pin "15") (pinfunction "RESV_15") (pintype "passive"))
      (node (ref "U2") (pin "8") (pinfunction "FSYNC_8") (pintype "passive"))
      (node (ref "U2") (pin "9") (pinfunction "RESV_9") (pintype "passive"))
      (node (ref "U3") (pin "22") (pinfunction "VSSRF_22") (pintype "power_in"))
      (node (ref "U3") (pin "32") (pinfunction "VSSSMPS_32") (pintype "power_in"))
      (node (ref "U3") (pin "49") (pinfunction "EP_49") (pintype "power_in"))
      (node (ref "U4") (pin "2") (pinfunction "GND_2") (pintype "passive"))
      (node (ref "U4") (pin "3") (pinfunction "CTL_3") (pintype "passive"))
      (node (ref "U5") (pin "2") (pinfunction "GND_2") (pintype "passive"))
      (node (ref "U5") (pin "25") (pinfunction "GND/PAD_25") (pintype "passive"))
      (node (ref "XTAL1") (pin "2") (pinfunction "2_2") (pintype "passive"))
      (node (ref "XTAL1") (pin "4") (pinfunction "4_4") (pintype "passive"))
    )
    (net (code "23") (name "Net-(ANT1-ANT)") (class "Default")
      (node (ref "ANT1") (pin "1") (pinfunction "ANT_1") (pintype "passive"))
      (node (ref "I3") (pin "2") (pinfunction "2_2") (pintype "passive"))
      (node (ref "I5") (pin "2") (pinfunction "2_2") (pintype "passive"))
    )
    (net (code "24") (name "Net-(D1-Pad1)") (class "Default")
      (node (ref "D1") (pin "1") (pinfunction "1_1") (pintype "passive"))
      (node (ref "R1") (pin "2") (pinfunction "2_2") (pintype "passive"))
    )
    (net (code "25") (name "Net-(D1-Pad4)") (class "Default")
      (node (ref "D1") (pin "4") (pinfunction "4_4") (pintype "passive"))
      (node (ref "R2") (pin "2") (pinfunction "2_2") (pintype "passive"))
    )
    (net (code "26") (name "Net-(D3-D)") (class "Default")
      (node (ref "D3") (pin "3") (pinfunction "D_3") (pintype "passive"))
      (node (ref "J1") (pin "1") (pinfunction "1_1") (pintype "passive"))
      (node (ref "U4") (pin "1") (pinfunction "VIN_1") (pintype "passive"))
    )
    (net (code "27") (name "Net-(D3-G)") (class "Default")
      (node (ref "D3") (pin "1") (pinfunction "G_1") (pintype "passive"))
      (node (ref "U4") (pin "5") (pinfunction "GATE_5") (pintype "passive"))
    )
    (net (code "28") (name "Net-(D3-S)") (class "Default")
      (node (ref "C1") (pin "2") (pinfunction "2_2") (pintype "passive"))
      (node (ref "C8") (pin "2") (pinfunction "2_2") (pintype "passive"))
      (node (ref "C9") (pin "2") (pinfunction "2_2") (pintype "passive"))
      (node (ref "D2") (pin "K") (pinfunction "K_K") (pintype "passive"))
      (node (ref "D3") (pin "2") (pinfunction "S_2") (pintype "passive"))
      (node (ref "U1") (pin "1") (pinfunction "Vin_1") (pintype "passive"))
      (node (ref "U1") (pin "2") (pinfunction "EN/UVLO_2") (pintype "passive"))
      (node (ref "U4") (pin "6") (pinfunction "SENSE_6") (pintype "passive"))
    )
    (net (code "29") (name "Net-(I6-Pad2)") (class "Default")
      (node (ref "I6") (pin "2") (pinfunction "2_2") (pintype "passive"))
      (node (ref "I7") (pin "1") (pinfunction "1_1") (pintype "passive"))
    )
    (net (code "30") (name "Net-(J3-CC1)") (class "Default")
      (node (ref "J3") (pin "A5") (pinfunction "CC1_A5") (pintype "passive"))
      (node (ref "R7") (pin "2") (pinfunction "2_2") (pintype "passive"))
    )
    (net (code "31") (name "Net-(J3-CC2)") (class "Default")
      (node (ref "J3") (pin "B5") (pinfunction "CC2_B5") (pintype "passive"))
      (node (ref "R5") (pin "2") (pinfunction "2_2") (pintype "passive"))
    )
    (net (code "32") (name "Net-(U1-LX)") (class "Default")
      (node (ref "I1") (pin "1") (pinfunction "1_1") (pintype "passive"))
      (node (ref "U1") (pin "8") (pinfunction "LX_8") (pintype "passive"))
    )
    (net (code "33") (name "Net-(U1-Vcc)") (class "Default")
      (node (ref "C5") (pin "2") (pinfunction "2_2") (pintype "passive"))
      (node (ref "U1") (pin "3") (pinfunction "Vcc_3") (pintype "passive"))
    )
    (net (code "34") (name "Net-(U2-REGOUT)") (class "Default")
      (node (ref "C7") (pin "2") (pinfunction "2_2") (pintype "passive"))
      (node (ref "U2") (pin "14") (pinfunction "REGOUT_14") (pintype "passive"))
    )
    (net (code "35") (name "Net-(U3-OSC_IN)") (class "Default")
      (node (ref "U3") (pin "25") (pinfunction "OSC_IN_25") (pintype "input"))
      (node (ref "XTAL1") (pin "3") (pinfunction "3_3") (pintype "passive"))
    )
    (net (code "36") (name "Net-(U3-OSC_OUT)") (class "Default")
      (node (ref "U3") (pin "24") (pinfunction "OSC_OUT_24") (pintype "output"))
      (node (ref "XTAL1") (pin "1") (pinfunction "1_1") (pintype "passive"))
    )
    (net (code "37") (name "Net-(U3-VFBSMPS)") (class "Default")
      (node (ref "C23") (pin "2") (pinfunction "2_2") (pintype "passive"))
      (node (ref "I7") (pin "2") (pinfunction "2_2") (pintype "passive"))
      (node (ref "U3") (pin "31") (pinfunction "VFBSMPS_31") (pintype "power_in"))
    )
    (net (code "38") (name "Net-(U3-VLXSMPS)") (class "Default")
      (node (ref "I6") (pin "1") (pinfunction "1_1") (pintype "passive"))
      (node (ref "U3") (pin "33") (pinfunction "VLXSMPS_33") (pintype "power_in"))
    )
    (net (code "39") (name "Net-(U5-~{RS}T)") (class "Default")
      (node (ref "R8") (pin "1") (pinfunction "1_1") (pintype "passive"))
      (node (ref "U5") (pin "9") (pinfunction "~{RS}T_9") (pintype "passive"))
    )
    (net (code "40") (name "unconnected-(ANT1-NC-Pad2)") (class "Default")
      (node (ref "ANT1") (pin "2") (pinfunction "NC_2") (pintype "passive+no_connect"))
    )
    (net (code "41") (name "unconnected-(J3-SBU1-PadA8)") (class "Default")
      (node (ref "J3") (pin "A8") (pinfunction "SBU1_A8") (pintype "passive+no_connect"))
    )
    (net (code "42") (name "unconnected-(J3-SBU2-PadB8)") (class "Default")
      (node (ref "J3") (pin "B8") (pinfunction "SBU2_B8") (pintype "passive+no_connect"))
    )
    (net (code "43") (name "unconnected-(U1-MODE-Pad5)") (class "Default")
      (node (ref "U1") (pin "5") (pinfunction "MODE_5") (pintype "passive+no_connect"))
    )
    (net (code "44") (name "unconnected-(U1-~{RESET}-Pad6)") (class "Default")
      (node (ref "U1") (pin "6") (pinfunction "~{RESET}_6") (pintype "passive+no_connect"))
    )
    (net (code "45") (name "unconnected-(U2-RESV_NC-Pad7)") (class "Default")
      (node (ref "U2") (pin "7") (pinfunction "RESV_NC_7") (pintype "passive+no_connect"))
    )
    (net (code "46") (name "unconnected-(U3-AT0-Pad26)") (class "Default")
      (node (ref "U3") (pin "26") (pinfunction "AT0_26") (pintype "output+no_connect"))
    )
    (net (code "47") (name "unconnected-(U3-AT1-Pad27)") (class "Default")
      (node (ref "U3") (pin "27") (pinfunction "AT1_27") (pintype "output+no_connect"))
    )
    (net (code "48") (name "unconnected-(U3-PA2-Pad11)") (class "Default")
      (node (ref "U3") (pin "11") (pinfunction "PA2_11") (pintype "bidirectional+no_connect"))
    )
    (net (code "49") (name "unconnected-(U3-PA3-Pad12)") (class "Default")
      (node (ref "U3") (pin "12") (pinfunction "PA3_12") (pintype "bidirectional+no_connect"))
    )
    (net (code "50") (name "unconnected-(U3-PA4-Pad13)") (class "Default")
      (node (ref "U3") (pin "13") (pinfunction "PA4_13") (pintype "bidirectional+no_connect"))
    )
    (net (code "51") (name "unconnected-(U3-PA5-Pad14)") (class "Default")
      (node (ref "U3") (pin "14") (pinfunction "PA5_14") (pintype "bidirectional+no_connect"))
    )
    (net (code "52") (name "unconnected-(U3-PA6-Pad15)") (class "Default")
      (node (ref "U3") (pin "15") (pinfunction "PA6_15") (pintype "bidirectional+no_connect"))
    )
    (net (code "53") (name "unconnected-(U3-PA7-Pad16)") (class "Default")
      (node (ref "U3") (pin "16") (pinfunction "PA7_16") (pintype "bidirectional+no_connect"))
    )
    (net (code "54") (name "unconnected-(U3-PA8-Pad17)") (class "Default")
      (node (ref "U3") (pin "17") (pinfunction "PA8_17") (pintype "bidirectional+no_connect"))
    )
    (net (code "55") (name "unconnected-(U3-PA11-Pad37)") (class "Default")
      (node (ref "U3") (pin "37") (pinfunction "PA11_37") (pintype "bidirectional+no_connect"))
    )
    (net (code "56") (name "unconnected-(U3-PA12-Pad38)") (class "Default")
      (node (ref "U3") (pin "38") (pinfunction "PA12_38") (pintype "bidirectional+no_connect"))
    )
    (net (code "57") (name "unconnected-(U3-PA15-Pad42)") (class "Default")
      (node (ref "U3") (pin "42") (pinfunction "PA15_42") (pintype "bidirectional+no_connect"))
    )
    (net (code "58") (name "unconnected-(U3-PB0-Pad28)") (class "Default")
      (node (ref "U3") (pin "28") (pinfunction "PB0_28") (pintype "bidirectional+no_connect"))
    )
    (net (code "59") (name "unconnected-(U3-PB1-Pad29)") (class "Default")
      (node (ref "U3") (pin "29") (pinfunction "PB1_29") (pintype "bidirectional+no_connect"))
    )
    (net (code "60") (name "unconnected-(U3-PB2-Pad19)") (class "Default")
      (node (ref "U3") (pin "19") (pinfunction "PB2_19") (pintype "bidirectional+no_connect"))
    )
    (net (code "61") (name "unconnected-(U3-PB4-Pad44)") (class "Default")
      (node (ref "U3") (pin "44") (pinfunction "PB4_44") (pintype "bidirectional+no_connect"))
    )
    (net (code "62") (name "unconnected-(U3-PB8-Pad5)") (class "Default")
      (node (ref "U3") (pin "5") (pinfunction "PB8_5") (pintype "bidirectional+no_connect"))
    )
    (net (code "63") (name "unconnected-(U3-PB9-Pad6)") (class "Default")
      (node (ref "U3") (pin "6") (pinfunction "PB9_6") (pintype "bidirectional+no_connect"))
    )
    (net (code "64") (name "unconnected-(U3-PC14-OSC32_IN-Pad2)") (class "Default")
      (node (ref "U3") (pin "2") (pinfunction "PC14-OSC32_IN_2") (pintype "bidirectional+no_connect"))
    )
    (net (code "65") (name "unconnected-(U3-PC15-OSC32_OUT-Pad3)") (class "Default")
      (node (ref "U3") (pin "3") (pinfunction "PC15-OSC32_OUT_3") (pintype "bidirectional+no_connect"))
    )
    (net (code "66") (name "unconnected-(U3-PE4-Pad30)") (class "Default")
      (node (ref "U3") (pin "30") (pinfunction "PE4_30") (pintype "bidirectional+no_connect"))
    )
    (net (code "67") (name "unconnected-(U4-STAT-Pad4)") (class "Default")
      (node (ref "U4") (pin "4") (pinfunction "STAT_4") (pintype "passive+no_connect"))
    )
    (net (code "68") (name "unconnected-(U5-CTS-Pad18)") (class "Default")
      (node (ref "U5") (pin "18") (pinfunction "CTS_18") (pintype "passive+no_connect"))
    )
    (net (code "69") (name "unconnected-(U5-DCD-Pad24)") (class "Default")
      (node (ref "U5") (pin "24") (pinfunction "DCD_24") (pintype "passive+no_connect"))
    )
    (net (code "70") (name "unconnected-(U5-DSR-Pad22)") (class "Default")
      (node (ref "U5") (pin "22") (pinfunction "DSR_22") (pintype "passive+no_connect"))
    )
    (net (code "71") (name "unconnected-(U5-DTR-Pad23)") (class "Default")
      (node (ref "U5") (pin "23") (pinfunction "DTR_23") (pintype "passive+no_connect"))
    )
    (net (code "72") (name "unconnected-(U5-GPIO0-Pad14)") (class "Default")
      (node (ref "U5") (pin "14") (pinfunction "GPIO0_14") (pintype "passive+no_connect"))
    )
    (net (code "73") (name "unconnected-(U5-GPIO1-Pad13)") (class "Default")
      (node (ref "U5") (pin "13") (pinfunction "GPIO1_13") (pintype "passive+no_connect"))
    )
    (net (code "74") (name "unconnected-(U5-GPIO2-Pad12)") (class "Default")
      (node (ref "U5") (pin "12") (pinfunction "GPIO2_12") (pintype "passive+no_connect"))
    )
    (net (code "75") (name "unconnected-(U5-GPIO3-Pad11)") (class "Default")
      (node (ref "U5") (pin "11") (pinfunction "GPIO3_11") (pintype "passive+no_connect"))
    )
    (net (code "76") (name "unconnected-(U5-NC-Pad10)") (class "Default")
      (node (ref "U5") (pin "10") (pinfunction "NC_10") (pintype "passive+no_connect"))
    )
    (net (code "77") (name "unconnected-(U5-RI-Pad1)") (class "Default")
      (node (ref "U5") (pin "1") (pinfunction "RI_1") (pintype "passive+no_connect"))
    )
    (net (code "78") (name "unconnected-(U5-RTS-Pad19)") (class "Default")
      (node (ref "U5") (pin "19") (pinfunction "RTS_19") (pintype "passive+no_connect"))
    )
    (net (code "79") (name "unconnected-(U5-SUSPEND-Pad17)") (class "Default")
      (node (ref "U5") (pin "17") (pinfunction "SUSPEND_17") (pintype "passive+no_connect"))
    )
    (net (code "80") (name "unconnected-(U5-VPP-Pad16)") (class "Default")
      (node (ref "U5") (pin "16") (pinfunction "VPP_16") (pintype "passive+no_connect"))
    )
    (net (code "81") (name "unconnected-(U5-~{SUSPEN}D-Pad15)") (class "Default")
      (node (ref "U5") (pin "15") (pinfunction "~{SUSPEN}D_15") (pintype "passive+no_connect"))
    )
  )
)
